# oshi-fuse-board-mk-2_mini-ato.net
KiCad netlist of a schematic drawn in EAGLE
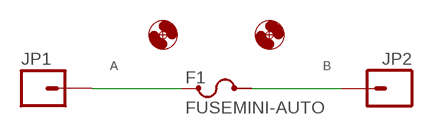
[diagram p0: schematic, sheet 1]

(export (version "E")
  (design (tool "Eeschema 10.0.6"))
  (components
    (comp (ref "F1")
      (value "FUSEMINI-AUTO")
      (footprint "eagle-import:KEYSTONE-MINI-AUTO-FUSE-HOLDER")
      (libsource (lib "eagle-import") (part "FUSEMINI-AUTO"))
    )
    (comp (ref "H1")
      (value "HOLE#4")
      (footprint "eagle-import:HOLE-#4")
      (libsource (lib "eagle-import") (part "HOLE#4"))
    )
    (comp (ref "H2")
      (value "HOLE#4")
      (footprint "eagle-import:HOLE-#4")
      (libsource (lib "eagle-import") (part "HOLE#4"))
    )
    (comp (ref "JP1")
      (value "M01SCREWITGOOD")
      (footprint "eagle-import:1X01-RING-TERM-6-32-FAT")
      (libsource (lib "eagle-import") (part "M01SCREWITGOOD"))
    )
    (comp (ref "JP2")
      (value "M01SCREWITGOOD")
      (footprint "eagle-import:1X01-RING-TERM-6-32-FAT")
      (libsource (lib "eagle-import") (part "M01SCREWITGOOD"))
    )
  )
  (nets
    (net (code "1") (name "/A") (class "Default")
      (node (ref "F1") (pin "P1@1") (pinfunction "1_P1@1") (pintype "passive"))
      (node (ref "F1") (pin "P1@2") (pinfunction "1_P1@2") (pintype "passive"))
      (node (ref "JP1") (pin "P$1") (pinfunction "1_P$1") (pintype "passive"))
      (node (ref "JP1") (pin "P$2") (pinfunction "1_P$2") (pintype "passive"))
      (node (ref "JP1") (pin "P$3") (pinfunction "1_P$3") (pintype "passive"))
      (node (ref "JP1") (pin "P$4") (pinfunction "1_P$4") (pintype "passive"))
    )
    (net (code "2") (name "/B") (class "Default")
      (node (ref "F1") (pin "P2@1") (pinfunction "2_P2@1") (pintype "passive"))
      (node (ref "F1") (pin "P2@2") (pinfunction "2_P2@2") (pintype "passive"))
      (node (ref "JP2") (pin "P$1") (pinfunction "1_P$1") (pintype "passive"))
      (node (ref "JP2") (pin "P$2") (pinfunction "1_P$2") (pintype "passive"))
      (node (ref "JP2") (pin "P$3") (pinfunction "1_P$3") (pintype "passive"))
      (node (ref "JP2") (pin "P$4") (pinfunction "1_P$4") (pintype "passive"))
    )
  )
)
